# MCU.net
KiCad netlist of a schematic drawn in Altium Designer
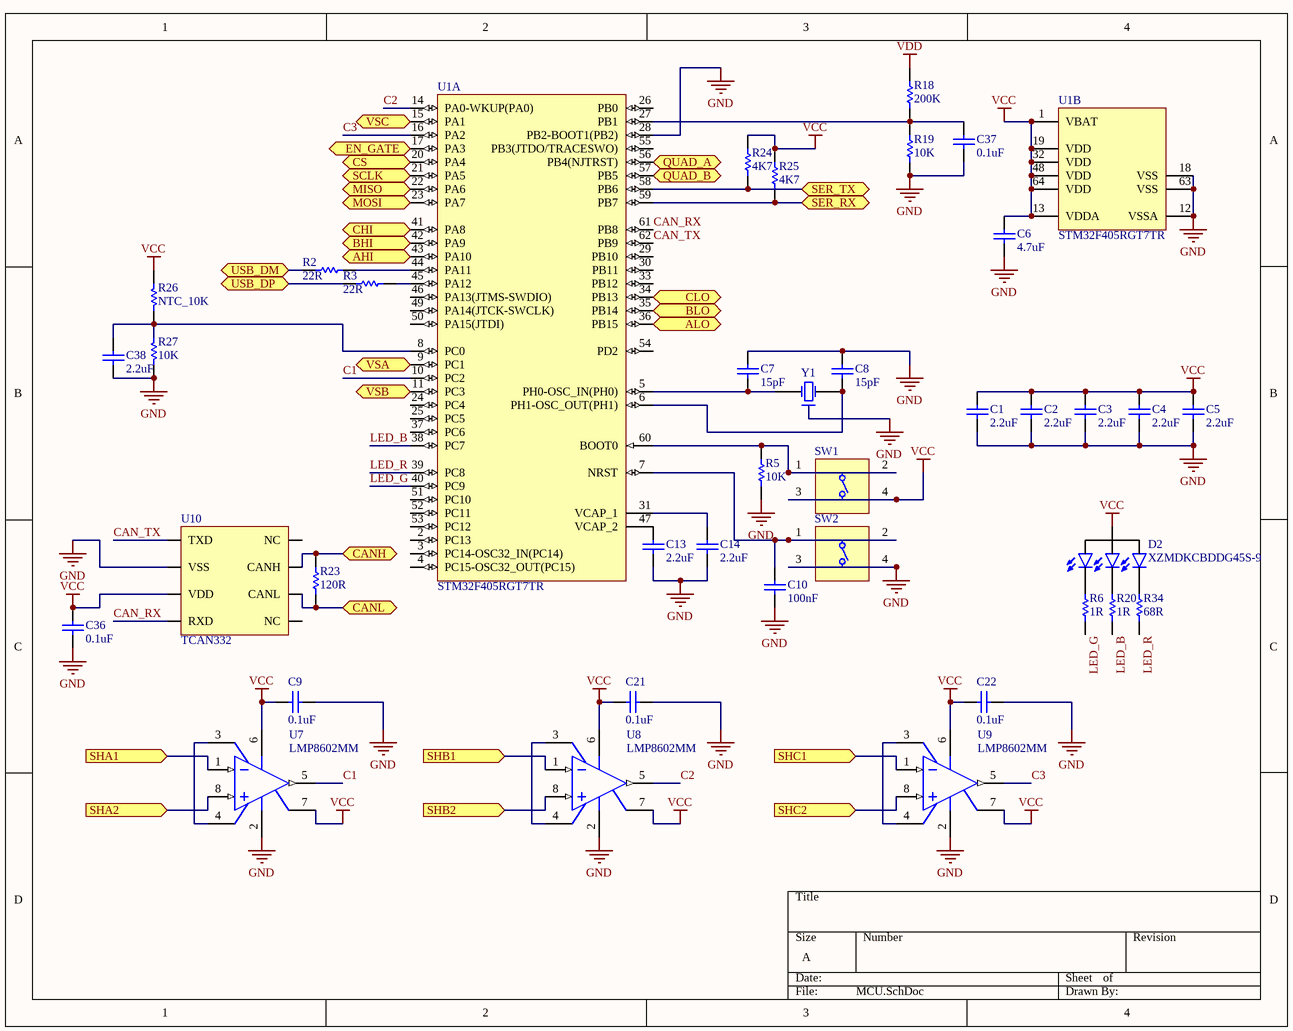
[diagram p0: MCU.SchDoc]

(export (version "E")
  (design (tool "Eeschema 10.0.6"))
  (components
    (comp (ref "C1")
      (value "2.2uF")
      (footprint "CAPC0402(1005)60_M")
      (description "CAP 2.2uF 6.3V ±10% 0402 (1005 Metric) Thickness 0.6mm SMD")
      (fields (field (name "TOLERANCE") "Â±10%"))
      (libsource (lib "Altium Content Vault") (part "CMP-1034-02125-1"))
    )
    (comp (ref "C2")
      (value "2.2uF")
      (footprint "CAPC0402(1005)60_M")
      (description "CAP 2.2uF 6.3V ±10% 0402 (1005 Metric) Thickness 0.6mm SMD")
      (fields (field (name "TOLERANCE") "Â±10%"))
      (libsource (lib "Altium Content Vault") (part "CMP-1034-02125-1"))
    )
    (comp (ref "C3")
      (value "2.2uF")
      (footprint "CAPC0402(1005)60_M")
      (description "CAP 2.2uF 6.3V ±10% 0402 (1005 Metric) Thickness 0.6mm SMD")
      (fields (field (name "TOLERANCE") "Â±10%"))
      (libsource (lib "Altium Content Vault") (part "CMP-1034-02125-1"))
    )
    (comp (ref "C4")
      (value "2.2uF")
      (footprint "CAPC0402(1005)60_M")
      (description "CAP 2.2uF 6.3V ±10% 0402 (1005 Metric) Thickness 0.6mm SMD")
      (fields (field (name "TOLERANCE") "Â±10%"))
      (libsource (lib "Altium Content Vault") (part "CMP-1034-02125-1"))
    )
    (comp (ref "C5")
      (value "2.2uF")
      (footprint "CAPC0402(1005)60_M")
      (description "CAP 2.2uF 6.3V ±10% 0402 (1005 Metric) Thickness 0.6mm SMD")
      (fields (field (name "TOLERANCE") "Â±10%"))
      (libsource (lib "Altium Content Vault") (part "CMP-1034-02125-1"))
    )
    (comp (ref "C6")
      (value "4.7uF")
      (footprint "CAPC0402(1005)60_L")
      (description "CAP 4.7uF 6.3V ±10% 0402 (1005 Metric) Thickness 0.6mm SMD")
      (fields (field (name "TOLERANCE") "Â±10%"))
      (libsource (lib "Altium Content Vault") (part "CMP-1034-02136-1"))
    )
    (comp (ref "C7")
      (value "15pF")
      (footprint "CAPC0402(1005)60_M")
      (description "CAP 15nF 6.3V ±10% 0402 (1005 Metric) Thickness 0.6mm SMD")
      (fields (field (name "TOLERANCE") "Â±10%"))
      (libsource (lib "Altium Content Vault") (part "CMP-1034-01906-1"))
    )
    (comp (ref "C8")
      (value "15pF")
      (footprint "CAPC0402(1005)60_M")
      (description "CAP 15nF 6.3V ±10% 0402 (1005 Metric) Thickness 0.6mm SMD")
      (fields (field (name "TOLERANCE") "Â±10%"))
      (libsource (lib "Altium Content Vault") (part "CMP-1034-01906-1"))
    )
    (comp (ref "C9")
      (value "0.1uF")
      (footprint "CAPC0402(1005)60_M")
      (description "CAP 100nF 6.3V ±5% 0402 (1005 Metric) Thickness 0.6mm SMD")
      (fields (field (name "TOLERANCE") "Â±5%"))
      (libsource (lib "Altium Content Vault") (part "CAP"))
    )
    (comp (ref "C10")
      (value "100nF")
      (footprint "CAPC0402(1005)60_L")
      (description "CAP 100nF 6.3V ±5% 0402 (1005 Metric) Thickness 0.6mm SMD")
      (fields (field (name "TOLERANCE") "Â±5%"))
      (libsource (lib "Altium Content Vault") (part "CMP-1034-02060-1"))
    )
    (comp (ref "C13")
      (value "2.2uF")
      (footprint "CAPC0402(1005)60_M")
      (description "CAP 2.2uF 6.3V ±10% 0402 (1005 Metric) Thickness 0.6mm SMD")
      (fields (field (name "TOLERANCE") "Â±10%"))
      (libsource (lib "Altium Content Vault") (part "CMP-1034-02125-1"))
    )
    (comp (ref "C14")
      (value "2.2uF")
      (footprint "CAPC0402(1005)60_M")
      (description "CAP 2.2uF 6.3V ±10% 0402 (1005 Metric) Thickness 0.6mm SMD")
      (fields (field (name "TOLERANCE") "Â±10%"))
      (libsource (lib "Altium Content Vault") (part "CMP-1034-02125-1"))
    )
    (comp (ref "C21")
      (value "0.1uF")
      (footprint "CAPC0402(1005)60_M")
      (description "CAP 100nF 6.3V ±5% 0402 (1005 Metric) Thickness 0.6mm SMD")
      (fields (field (name "TOLERANCE") "Â±5%"))
      (libsource (lib "Altium Content Vault") (part "CAP"))
    )
    (comp (ref "C22")
      (value "0.1uF")
      (footprint "CAPC0402(1005)60_M")
      (description "CAP 100nF 6.3V ±5% 0402 (1005 Metric) Thickness 0.6mm SMD")
      (fields (field (name "TOLERANCE") "Â±5%"))
      (libsource (lib "Altium Content Vault") (part "CAP"))
    )
    (comp (ref "C36")
      (value "0.1uF")
      (footprint "CAPC0402(1005)60_M")
      (description "CAP 100nF 6.3V ±5% 0402 (1005 Metric) Thickness 0.6mm SMD")
      (fields (field (name "TOLERANCE") "Â±5%"))
      (libsource (lib "Altium Content Vault") (part "CMP-1034-02060-1"))
    )
    (comp (ref "C37")
      (value "0.1uF")
      (footprint "CAPC0402(1005)60_L")
      (description "CAP 100nF 6.3V ±5% 0402 (1005 Metric) Thickness 0.6mm SMD")
      (fields (field (name "TOLERANCE") "Â±5%"))
      (libsource (lib "Altium Content Vault") (part "CMP-1034-02060-1"))
    )
    (comp (ref "C38")
      (value "2.2uF")
      (footprint "CAPC0402(1005)60_M")
      (description "CAP 2.2uF 6.3V ±10% 0402 (1005 Metric) Thickness 0.6mm SMD")
      (fields (field (name "TOLERANCE") "Â±10%"))
      (libsource (lib "Altium Content Vault") (part "CAP"))
    )
    (comp (ref "D2")
      (value "XZMDKCBDDG45S-9")
      (footprint "XZMDKCBDDG45S-9")
      (libsource (lib "Components") (part "XZMDKCBDDG45S-9"))
    )
    (comp (ref "R2")
      (value "22R")
      (footprint "RESC0402(1005)_L")
      (description "22R 0.063W 5% 0402 (1005 Metric)  SMD")
      (fields (field (name "POWER") "0.063 W") (field (name "TOLERANCE") "5 %"))
      (libsource (lib "Altium Content Vault") (part "CMP-1011-00034-1"))
    )
    (comp (ref "R3")
      (value "22R")
      (footprint "RESC0402(1005)_L")
      (description "22R 0.063W 5% 0402 (1005 Metric)  SMD")
      (fields (field (name "POWER") "0.063 W") (field (name "TOLERANCE") "5 %"))
      (libsource (lib "Altium Content Vault") (part "CMP-1011-00034-1"))
    )
    (comp (ref "R5")
      (value "10K")
      (footprint "RESC0402(1005)_L")
      (description "10K 0.063W 5% 0402 (1005 Metric)  SMD")
      (fields (field (name "TOLERANCE") "5 %") (field (name "POWER") "0.063 W"))
      (libsource (lib "Altium Content Vault") (part "CMP-1011-00098-1"))
    )
    (comp (ref "R6")
      (value "1R")
      (footprint "RESC0402(1005)_N")
      (description "1R 0.063W 5% 0402 (1005 Metric)  SMD")
      (fields (field (name "POWER") "0.063 W") (field (name "TOLERANCE") "5 %"))
      (libsource (lib "Altium Content Vault") (part "RES"))
    )
    (comp (ref "R18")
      (value "200K")
      (footprint "RESC0402(1005)_N")
      (description "5K1 0.063W 5% 0402 (1005 Metric)  SMD")
      (fields (field (name "TOLERANCE") "5 %") (field (name "POWER") "0.063 W"))
      (libsource (lib "Altium Content Vault") (part "CMP-1011-00091-1"))
    )
    (comp (ref "R19")
      (value "10K")
      (footprint "RESC0402(1005)_N")
      (description "10K 0.063W 5% 0402 (1005 Metric)  SMD")
      (fields (field (name "TOLERANCE") "5 %") (field (name "POWER") "0.063 W"))
      (libsource (lib "Altium Content Vault") (part "RES"))
    )
    (comp (ref "R20")
      (value "1R")
      (footprint "RESC0402(1005)_N")
      (description "1R 0.063W 5% 0402 (1005 Metric)  SMD")
      (fields (field (name "POWER") "0.063 W") (field (name "TOLERANCE") "5 %"))
      (libsource (lib "Altium Content Vault") (part "RES"))
    )
    (comp (ref "R23")
      (value "120R")
      (footprint "RESC0402(1005)_N")
      (description "120R 0.063W 5% 0402 (1005 Metric)  SMD")
      (fields (field (name "TOLERANCE") "5 %") (field (name "POWER") "0.063 W"))
      (libsource (lib "Altium Content Vault") (part "RES"))
    )
    (comp (ref "R24")
      (value "4K7")
      (footprint "RESC0402(1005)_L")
      (description "4K7 0.063W 5% 0402 (1005 Metric)  SMD")
      (fields (field (name "TOLERANCE") "5 %") (field (name "POWER") "0.063 W"))
      (libsource (lib "Altium Content Vault") (part "RES"))
    )
    (comp (ref "R25")
      (value "4K7")
      (footprint "RESC0402(1005)_L")
      (description "4K7 0.063W 5% 0402 (1005 Metric)  SMD")
      (fields (field (name "TOLERANCE") "5 %") (field (name "POWER") "0.063 W"))
      (libsource (lib "Altium Content Vault") (part "RES"))
    )
    (comp (ref "R26")
      (value "NTC_10K")
      (footprint "RESC0402(1005)_L")
      (description "10K 0.063W 1% 0402 (1005 Metric)  SMD")
      (fields (field (name "TOLERANCE") "1 %") (field (name "POWER") "0.063 W"))
      (libsource (lib "Altium Content Vault") (part "CMP-1011-00623-1"))
    )
    (comp (ref "R27")
      (value "10K")
      (footprint "RESC0402(1005)_L")
      (description "10K 0.063W 1% 0402 (1005 Metric)  SMD")
      (fields (field (name "TOLERANCE") "1 %") (field (name "POWER") "0.063 W"))
      (libsource (lib "Altium Content Vault") (part "CMP-1011-00623-1"))
    )
    (comp (ref "R34")
      (value "68R")
      (footprint "RESC0402(1005)_N")
      (description "68R 0.063W 5% 0402 (1005 Metric)  SMD")
      (fields (field (name "TOLERANCE") "5 %") (field (name "POWER") "0.063 W"))
      (libsource (lib "Altium Content Vault") (part "RES"))
    )
    (comp (ref "SW1")
      (value "~")
      (footprint "SWITCH")
      (description "Switch, SPNO Push Button SMD")
      (fields (field (name "MANUFACTURER") "Diptronics") (field (name "PARTNUMBER") "DTSM-61NT/R"))
      (libsource (lib "altium-import") (part "root_0_DIPT-DTSM-6_"))
    )
    (comp (ref "SW2")
      (value "~")
      (footprint "SWITCH")
      (description "Switch, SPNO Push Button SMD")
      (fields (field (name "MANUFACTURER") "Diptronics") (field (name "PARTNUMBER") "DTSM-61NT/R"))
      (libsource (lib "altium-import") (part "root_0_DIPT-DTSM-6_"))
    )
    (comp (ref "U1")
      (value "STM32F405RGT7TR")
      (footprint "STM-LQFP64_V")
      (fields (field (name "MANUFACTURER") "STMicroelectronics"))
      (libsource (lib "Altium Content Vault") (part "MC-ARM-STM32F4X5-SQ64"))
    )
    (comp (ref "U7")
      (value "LMP8602MM")
      (footprint "MUA08A_L")
      (fields (field (name "MANUFACTURER") "National Semiconductor"))
      (libsource (lib "Altium Content Vault") (part "AMP-SEN-LMP8601-8"))
    )
    (comp (ref "U8")
      (value "LMP8602MM")
      (footprint "MUA08A_L")
      (fields (field (name "MANUFACTURER") "National Semiconductor"))
      (libsource (lib "Altium Content Vault") (part "AMP-SEN-LMP8601-8"))
    )
    (comp (ref "U9")
      (value "LMP8602MM")
      (footprint "MUA08A_L")
      (fields (field (name "MANUFACTURER") "National Semiconductor"))
      (libsource (lib "Altium Content Vault") (part "AMP-SEN-LMP8601-8"))
    )
    (comp (ref "U10")
      (value "TCAN332")
      (footprint "SOT65P280X145-6N")
      (libsource (lib "Components") (part "TCAN332"))
    )
    (comp (ref "Y1")
      (value "~")
      (footprint "ABRA-ABM3B-4_V")
      (libsource (lib "Components") (part "ABRA-ABM3B-4"))
    )
  )
  (nets
    (net (code "1") (name "/AHI") (class "Default")
      (node (ref "U1") (pin "43") (pinfunction "PA10_43") (pintype "bidirectional"))
    )
    (net (code "2") (name "/ALO") (class "Default")
      (node (ref "U1") (pin "36") (pinfunction "PB15_36") (pintype "bidirectional"))
    )
    (net (code "3") (name "/BHI") (class "Default")
      (node (ref "U1") (pin "42") (pinfunction "PA9_42") (pintype "bidirectional"))
    )
    (net (code "4") (name "/BLO") (class "Default")
      (node (ref "U1") (pin "35") (pinfunction "PB14_35") (pintype "bidirectional"))
    )
    (net (code "5") (name "/C1") (class "Default")
      (node (ref "U1") (pin "10") (pinfunction "PC2_10") (pintype "bidirectional"))
      (node (ref "U7") (pin "5") (pinfunction "OUT_5") (pintype "output"))
    )
    (net (code "6") (name "/C2") (class "Default")
      (node (ref "U1") (pin "14") (pinfunction "PA0-WKUP(PA0)_14") (pintype "bidirectional"))
      (node (ref "U8") (pin "5") (pinfunction "OUT_5") (pintype "output"))
    )
    (net (code "7") (name "/C3") (class "Default")
      (node (ref "U1") (pin "16") (pinfunction "PA2_16") (pintype "bidirectional"))
      (node (ref "U9") (pin "5") (pinfunction "OUT_5") (pintype "output"))
    )
    (net (code "8") (name "/CANH") (class "Default")
      (node (ref "R23") (pin "2") (pinfunction "2_2") (pintype "passive"))
      (node (ref "U10") (pin "7") (pinfunction "CANH_7") (pintype "passive"))
    )
    (net (code "9") (name "/CANL") (class "Default")
      (node (ref "R23") (pin "1") (pinfunction "1_1") (pintype "passive"))
      (node (ref "U10") (pin "6") (pinfunction "CANL_6") (pintype "passive"))
    )
    (net (code "10") (name "/CAN_RX") (class "Default")
      (node (ref "U1") (pin "61") (pinfunction "PB8_61") (pintype "bidirectional"))
      (node (ref "U10") (pin "4") (pinfunction "RXD_4") (pintype "passive"))
    )
    (net (code "11") (name "/CAN_TX") (class "Default")
      (node (ref "U1") (pin "62") (pinfunction "PB9_62") (pintype "bidirectional"))
      (node (ref "U10") (pin "1") (pinfunction "TXD_1") (pintype "passive"))
    )
    (net (code "12") (name "/CHI") (class "Default")
      (node (ref "U1") (pin "41") (pinfunction "PA8_41") (pintype "bidirectional"))
    )
    (net (code "13") (name "/CLO") (class "Default")
      (node (ref "U1") (pin "34") (pinfunction "PB13_34") (pintype "bidirectional"))
    )
    (net (code "14") (name "/CS") (class "Default")
      (node (ref "U1") (pin "20") (pinfunction "PA4_20") (pintype "bidirectional"))
    )
    (net (code "15") (name "/EN_GATE") (class "Default")
      (node (ref "U1") (pin "17") (pinfunction "PA3_17") (pintype "bidirectional"))
    )
    (net (code "16") (name "/LED_B") (class "Default")
      (node (ref "R20") (pin "1") (pinfunction "1_1") (pintype "passive"))
      (node (ref "U1") (pin "38") (pinfunction "PC7_38") (pintype "bidirectional"))
    )
    (net (code "17") (name "/LED_G") (class "Default")
      (node (ref "R6") (pin "1") (pinfunction "1_1") (pintype "passive"))
      (node (ref "U1") (pin "40") (pinfunction "PC9_40") (pintype "bidirectional"))
    )
    (net (code "18") (name "/LED_R") (class "Default")
      (node (ref "R34") (pin "1") (pinfunction "1_1") (pintype "passive"))
      (node (ref "U1") (pin "39") (pinfunction "PC8_39") (pintype "bidirectional"))
    )
    (net (code "19") (name "/MISO") (class "Default")
      (node (ref "U1") (pin "22") (pinfunction "PA6_22") (pintype "bidirectional"))
    )
    (net (code "20") (name "/MOSI") (class "Default")
      (node (ref "U1") (pin "23") (pinfunction "PA7_23") (pintype "bidirectional"))
    )
    (net (code "21") (name "/QUAD_A") (class "Default")
      (node (ref "U1") (pin "56") (pinfunction "PB4(NJTRST)_56") (pintype "bidirectional"))
    )
    (net (code "22") (name "/QUAD_B") (class "Default")
      (node (ref "U1") (pin "57") (pinfunction "PB5_57") (pintype "bidirectional"))
    )
    (net (code "23") (name "/SCLK") (class "Default")
      (node (ref "U1") (pin "21") (pinfunction "PA5_21") (pintype "bidirectional"))
    )
    (net (code "24") (name "/SER_RX") (class "Default")
      (node (ref "R25") (pin "1") (pinfunction "1_1") (pintype "passive"))
      (node (ref "U1") (pin "59") (pinfunction "PB7_59") (pintype "bidirectional"))
    )
    (net (code "25") (name "/SER_TX") (class "Default")
      (node (ref "R24") (pin "1") (pinfunction "1_1") (pintype "passive"))
      (node (ref "U1") (pin "58") (pinfunction "PB6_58") (pintype "bidirectional"))
    )
    (net (code "26") (name "/SHA1") (class "Default")
      (node (ref "U7") (pin "1") (pinfunction "IN-_1") (pintype "input"))
    )
    (net (code "27") (name "/SHA2") (class "Default")
      (node (ref "U7") (pin "8") (pinfunction "IN+_8") (pintype "input"))
    )
    (net (code "28") (name "/SHB1") (class "Default")
      (node (ref "U8") (pin "1") (pinfunction "IN-_1") (pintype "input"))
    )
    (net (code "29") (name "/SHB2") (class "Default")
      (node (ref "U8") (pin "8") (pinfunction "IN+_8") (pintype "input"))
    )
    (net (code "30") (name "/SHC1") (class "Default")
      (node (ref "U9") (pin "1") (pinfunction "IN-_1") (pintype "input"))
    )
    (net (code "31") (name "/SHC2") (class "Default")
      (node (ref "U9") (pin "8") (pinfunction "IN+_8") (pintype "input"))
    )
    (net (code "32") (name "/USB_DM") (class "Default")
      (node (ref "R2") (pin "1") (pinfunction "1_1") (pintype "passive"))
    )
    (net (code "33") (name "/USB_DP") (class "Default")
      (node (ref "R3") (pin "1") (pinfunction "1_1") (pintype "passive"))
    )
    (net (code "34") (name "/VSA") (class "Default")
      (node (ref "U1") (pin "9") (pinfunction "PC1_9") (pintype "bidirectional"))
    )
    (net (code "35") (name "/VSB") (class "Default")
      (node (ref "U1") (pin "11") (pinfunction "PC3_11") (pintype "bidirectional"))
    )
    (net (code "36") (name "/VSC") (class "Default")
      (node (ref "U1") (pin "15") (pinfunction "PA1_15") (pintype "bidirectional"))
    )
    (net (code "37") (name "GND") (class "Default")
      (node (ref "C1") (pin "1") (pinfunction "1_1") (pintype "passive"))
      (node (ref "C10") (pin "1") (pinfunction "1_1") (pintype "passive"))
      (node (ref "C13") (pin "1") (pinfunction "1_1") (pintype "passive"))
      (node (ref "C14") (pin "1") (pinfunction "1_1") (pintype "passive"))
      (node (ref "C2") (pin "1") (pinfunction "1_1") (pintype "passive"))
      (node (ref "C21") (pin "2") (pinfunction "2_2") (pintype "passive"))
      (node (ref "C22") (pin "2") (pinfunction "2_2") (pintype "passive"))
      (node (ref "C3") (pin "1") (pinfunction "1_1") (pintype "passive"))
      (node (ref "C36") (pin "1") (pinfunction "1_1") (pintype "passive"))
      (node (ref "C37") (pin "1") (pinfunction "1_1") (pintype "passive"))
      (node (ref "C38") (pin "1") (pinfunction "1_1") (pintype "passive"))
      (node (ref "C4") (pin "1") (pinfunction "1_1") (pintype "passive"))
      (node (ref "C5") (pin "1") (pinfunction "1_1") (pintype "passive"))
      (node (ref "C6") (pin "1") (pinfunction "1_1") (pintype "passive"))
      (node (ref "C7") (pin "2") (pinfunction "2_2") (pintype "passive"))
      (node (ref "C8") (pin "2") (pinfunction "2_2") (pintype "passive"))
      (node (ref "C9") (pin "2") (pinfunction "2_2") (pintype "passive"))
      (node (ref "R19") (pin "1") (pinfunction "1_1") (pintype "passive"))
      (node (ref "R27") (pin "1") (pinfunction "1_1") (pintype "passive"))
      (node (ref "R5") (pin "1") (pinfunction "1_1") (pintype "passive"))
      (node (ref "SW2") (pin "3") (pinfunction "T3_3") (pintype "passive"))
      (node (ref "SW2") (pin "4") (pinfunction "T3_4") (pintype "passive"))
      (node (ref "U1") (pin "12") (pinfunction "VSSA_12") (pintype "power_in"))
      (node (ref "U1") (pin "18") (pinfunction "VSS_18") (pintype "power_in"))
      (node (ref "U1") (pin "28") (pinfunction "PB2-BOOT1(PB2)_28") (pintype "bidirectional"))
      (node (ref "U1") (pin "63") (pinfunction "VSS_63") (pintype "power_in"))
      (node (ref "U10") (pin "2") (pinfunction "VSS_2") (pintype "passive"))
      (node (ref "U7") (pin "2") (pinfunction "GND_2") (pintype "power_in"))
      (node (ref "U8") (pin "2") (pinfunction "GND_2") (pintype "power_in"))
      (node (ref "U9") (pin "2") (pinfunction "GND_2") (pintype "power_in"))
      (node (ref "Y1") (pin "2") (pinfunction "2_2") (pintype "passive"))
    )
    (net (code "38") (name "Net-(D2-K_Blue)") (class "Default")
      (node (ref "D2") (pin "3") (pinfunction "K_Blue_3") (pintype "passive"))
      (node (ref "R20") (pin "2") (pinfunction "2_2") (pintype "passive"))
    )
    (net (code "39") (name "Net-(D2-K_Green)") (class "Default")
      (node (ref "D2") (pin "4") (pinfunction "K_Green_4") (pintype "passive"))
      (node (ref "R6") (pin "2") (pinfunction "2_2") (pintype "passive"))
    )
    (net (code "40") (name "Net-(D2-K_Red)") (class "Default")
      (node (ref "D2") (pin "1") (pinfunction "K_Red_1") (pintype "passive"))
      (node (ref "R34") (pin "2") (pinfunction "2_2") (pintype "passive"))
    )
    (net (code "41") (name "Net-(SW1-T1)") (class "Default")
      (node (ref "R5") (pin "2") (pinfunction "2_2") (pintype "passive"))
      (node (ref "SW1") (pin "1") (pinfunction "T1_1") (pintype "passive"))
      (node (ref "SW1") (pin "2") (pinfunction "T2_2") (pintype "passive"))
      (node (ref "U1") (pin "60") (pinfunction "BOOT0_60") (pintype "input"))
    )
    (net (code "42") (name "Net-(SW2-T1)") (class "Default")
      (node (ref "C10") (pin "2") (pinfunction "2_2") (pintype "passive"))
      (node (ref "SW2") (pin "1") (pinfunction "T1_1") (pintype "passive"))
      (node (ref "SW2") (pin "2") (pinfunction "T2_2") (pintype "passive"))
      (node (ref "U1") (pin "7") (pinfunction "NRST_7") (pintype "bidirectional"))
    )
    (net (code "43") (name "Net-(U1A-PA11)") (class "Default")
      (node (ref "R2") (pin "2") (pinfunction "2_2") (pintype "passive"))
      (node (ref "U1") (pin "44") (pinfunction "PA11_44") (pintype "bidirectional"))
    )
    (net (code "44") (name "Net-(U1A-PA12)") (class "Default")
      (node (ref "R3") (pin "2") (pinfunction "2_2") (pintype "passive"))
      (node (ref "U1") (pin "45") (pinfunction "PA12_45") (pintype "bidirectional"))
    )
    (net (code "45") (name "Net-(U1A-PB1)") (class "Default")
      (node (ref "C37") (pin "2") (pinfunction "2_2") (pintype "passive"))
      (node (ref "R18") (pin "2") (pinfunction "2_2") (pintype "passive"))
      (node (ref "R19") (pin "2") (pinfunction "2_2") (pintype "passive"))
      (node (ref "U1") (pin "27") (pinfunction "PB1_27") (pintype "bidirectional"))
    )
    (net (code "46") (name "Net-(U1A-PC0)") (class "Default")
      (node (ref "C38") (pin "2") (pinfunction "2_2") (pintype "passive"))
      (node (ref "R26") (pin "1") (pinfunction "1_1") (pintype "passive"))
      (node (ref "R27") (pin "2") (pinfunction "2_2") (pintype "passive"))
      (node (ref "U1") (pin "8") (pinfunction "PC0_8") (pintype "bidirectional"))
    )
    (net (code "47") (name "Net-(U1A-PH0-OSC_IN(PH0))") (class "Default")
      (node (ref "C7") (pin "1") (pinfunction "1_1") (pintype "passive"))
      (node (ref "U1") (pin "5") (pinfunction "PH0-OSC_IN(PH0)_5") (pintype "bidirectional"))
      (node (ref "Y1") (pin "1") (pinfunction "X1_1") (pintype "passive"))
    )
    (net (code "48") (name "Net-(U1A-PH1-OSC_OUT(PH1))") (class "Default")
      (node (ref "C8") (pin "1") (pinfunction "1_1") (pintype "passive"))
      (node (ref "U1") (pin "6") (pinfunction "PH1-OSC_OUT(PH1)_6") (pintype "bidirectional"))
      (node (ref "Y1") (pin "3") (pinfunction "X2_3") (pintype "passive"))
    )
    (net (code "49") (name "Net-(U1A-VCAP_1)") (class "Default")
      (node (ref "C14") (pin "2") (pinfunction "2_2") (pintype "passive"))
      (node (ref "U1") (pin "31") (pinfunction "VCAP_1_31") (pintype "power_in"))
    )
    (net (code "50") (name "Net-(U1A-VCAP_2)") (class "Default")
      (node (ref "C13") (pin "2") (pinfunction "2_2") (pintype "passive"))
      (node (ref "U1") (pin "47") (pinfunction "VCAP_2_47") (pintype "power_in"))
    )
    (net (code "51") (name "Net-(U7-A1)") (class "Default")
      (node (ref "U7") (pin "3") (pinfunction "A1_3") (pintype "passive"))
      (node (ref "U7") (pin "4") (pinfunction "A2_4") (pintype "passive"))
    )
    (net (code "52") (name "Net-(U8-A1)") (class "Default")
      (node (ref "U8") (pin "3") (pinfunction "A1_3") (pintype "passive"))
      (node (ref "U8") (pin "4") (pinfunction "A2_4") (pintype "passive"))
    )
    (net (code "53") (name "Net-(U9-A1)") (class "Default")
      (node (ref "U9") (pin "3") (pinfunction "A1_3") (pintype "passive"))
      (node (ref "U9") (pin "4") (pinfunction "A2_4") (pintype "passive"))
    )
    (net (code "54") (name "VCC") (class "Default")
      (node (ref "C1") (pin "2") (pinfunction "2_2") (pintype "passive"))
      (node (ref "C2") (pin "2") (pinfunction "2_2") (pintype "passive"))
      (node (ref "C21") (pin "1") (pinfunction "1_1") (pintype "passive"))
      (node (ref "C22") (pin "1") (pinfunction "1_1") (pintype "passive"))
      (node (ref "C3") (pin "2") (pinfunction "2_2") (pintype "passive"))
      (node (ref "C36") (pin "2") (pinfunction "2_2") (pintype "passive"))
      (node (ref "C4") (pin "2") (pinfunction "2_2") (pintype "passive"))
      (node (ref "C5") (pin "2") (pinfunction "2_2") (pintype "passive"))
      (node (ref "C6") (pin "2") (pinfunction "2_2") (pintype "passive"))
      (node (ref "C9") (pin "1") (pinfunction "1_1") (pintype "passive"))
      (node (ref "D2") (pin "2") (pinfunction "A_2") (pintype "passive"))
      (node (ref "R24") (pin "2") (pinfunction "2_2") (pintype "passive"))
      (node (ref "R25") (pin "2") (pinfunction "2_2") (pintype "passive"))
      (node (ref "R26") (pin "2") (pinfunction "2_2") (pintype "passive"))
      (node (ref "SW1") (pin "3") (pinfunction "T3_3") (pintype "passive"))
      (node (ref "SW1") (pin "4") (pinfunction "T3_4") (pintype "passive"))
      (node (ref "U1") (pin "1") (pinfunction "VBAT_1") (pintype "power_in"))
      (node (ref "U1") (pin "13") (pinfunction "VDDA_13") (pintype "power_in"))
      (node (ref "U1") (pin "19") (pinfunction "VDD_19") (pintype "power_in"))
      (node (ref "U1") (pin "32") (pinfunction "VDD_32") (pintype "power_in"))
      (node (ref "U1") (pin "48") (pinfunction "VDD_48") (pintype "power_in"))
      (node (ref "U1") (pin "64") (pinfunction "VDD_64") (pintype "power_in"))
      (node (ref "U10") (pin "3") (pinfunction "VDD_3") (pintype "passive"))
      (node (ref "U7") (pin "6") (pinfunction "VS_6") (pintype "power_in"))
      (node (ref "U7") (pin "7") (pinfunction "OFS_7") (pintype "passive"))
      (node (ref "U8") (pin "6") (pinfunction "VS_6") (pintype "power_in"))
      (node (ref "U8") (pin "7") (pinfunction "OFS_7") (pintype "passive"))
      (node (ref "U9") (pin "6") (pinfunction "VS_6") (pintype "power_in"))
      (node (ref "U9") (pin "7") (pinfunction "OFS_7") (pintype "passive"))
    )
    (net (code "55") (name "VDD") (class "Default")
      (node (ref "R18") (pin "1") (pinfunction "1_1") (pintype "passive"))
    )
    (net (code "56") (name "unconnected-(U1A-PA13(JTMS-SWDIO)-Pad46)") (class "Default")
      (node (ref "U1") (pin "46") (pinfunction "PA13(JTMS-SWDIO)_46") (pintype "bidirectional"))
    )
    (net (code "57") (name "unconnected-(U1A-PA14(JTCK-SWCLK)-Pad49)") (class "Default")
      (node (ref "U1") (pin "49") (pinfunction "PA14(JTCK-SWCLK)_49") (pintype "bidirectional"))
    )
    (net (code "58") (name "unconnected-(U1A-PA15(JTDI)-Pad50)") (class "Default")
      (node (ref "U1") (pin "50") (pinfunction "PA15(JTDI)_50") (pintype "bidirectional"))
    )
    (net (code "59") (name "unconnected-(U1A-PB0-Pad26)") (class "Default")
      (node (ref "U1") (pin "26") (pinfunction "PB0_26") (pintype "bidirectional"))
    )
    (net (code "60") (name "unconnected-(U1A-PB3(JTDO{slash}TRACESWO)-Pad55)") (class "Default")
      (node (ref "U1") (pin "55") (pinfunction "PB3(JTDO/TRACESWO)_55") (pintype "bidirectional"))
    )
    (net (code "61") (name "unconnected-(U1A-PB10-Pad29)") (class "Default")
      (node (ref "U1") (pin "29") (pinfunction "PB10_29") (pintype "bidirectional"))
    )
    (net (code "62") (name "unconnected-(U1A-PB11-Pad30)") (class "Default")
      (node (ref "U1") (pin "30") (pinfunction "PB11_30") (pintype "bidirectional"))
    )
    (net (code "63") (name "unconnected-(U1A-PB12-Pad33)") (class "Default")
      (node (ref "U1") (pin "33") (pinfunction "PB12_33") (pintype "bidirectional"))
    )
    (net (code "64") (name "unconnected-(U1A-PC4-Pad24)") (class "Default")
      (node (ref "U1") (pin "24") (pinfunction "PC4_24") (pintype "bidirectional"))
    )
    (net (code "65") (name "unconnected-(U1A-PC5-Pad25)") (class "Default")
      (node (ref "U1") (pin "25") (pinfunction "PC5_25") (pintype "bidirectional"))
    )
    (net (code "66") (name "unconnected-(U1A-PC6-Pad37)") (class "Default")
      (node (ref "U1") (pin "37") (pinfunction "PC6_37") (pintype "bidirectional"))
    )
    (net (code "67") (name "unconnected-(U1A-PC10-Pad51)") (class "Default")
      (node (ref "U1") (pin "51") (pinfunction "PC10_51") (pintype "bidirectional"))
    )
    (net (code "68") (name "unconnected-(U1A-PC11-Pad52)") (class "Default")
      (node (ref "U1") (pin "52") (pinfunction "PC11_52") (pintype "bidirectional"))
    )
    (net (code "69") (name "unconnected-(U1A-PC12-Pad53)") (class "Default")
      (node (ref "U1") (pin "53") (pinfunction "PC12_53") (pintype "bidirectional"))
    )
    (net (code "70") (name "unconnected-(U1A-PC13-Pad2)") (class "Default")
      (node (ref "U1") (pin "2") (pinfunction "PC13_2") (pintype "bidirectional"))
    )
    (net (code "71") (name "unconnected-(U1A-PC14-OSC32_IN(PC14)-Pad3)") (class "Default")
      (node (ref "U1") (pin "3") (pinfunction "PC14-OSC32_IN(PC14)_3") (pintype "bidirectional"))
    )
    (net (code "72") (name "unconnected-(U1A-PC15-OSC32_OUT(PC15)-Pad4)") (class "Default")
      (node (ref "U1") (pin "4") (pinfunction "PC15-OSC32_OUT(PC15)_4") (pintype "bidirectional"))
    )
    (net (code "73") (name "unconnected-(U1A-PD2-Pad54)") (class "Default")
      (node (ref "U1") (pin "54") (pinfunction "PD2_54") (pintype "bidirectional"))
    )
    (net (code "74") (name "unconnected-(U10-NC-Pad5)") (class "Default")
      (node (ref "U10") (pin "5") (pinfunction "NC_5") (pintype "passive"))
    )
    (net (code "75") (name "unconnected-(U10-NC-Pad8)") (class "Default")
      (node (ref "U10") (pin "8") (pinfunction "NC_8") (pintype "passive"))
    )
  )
)
